# fDrive_RP2040.net
KiCad netlist of a schematic drawn in EAGLE
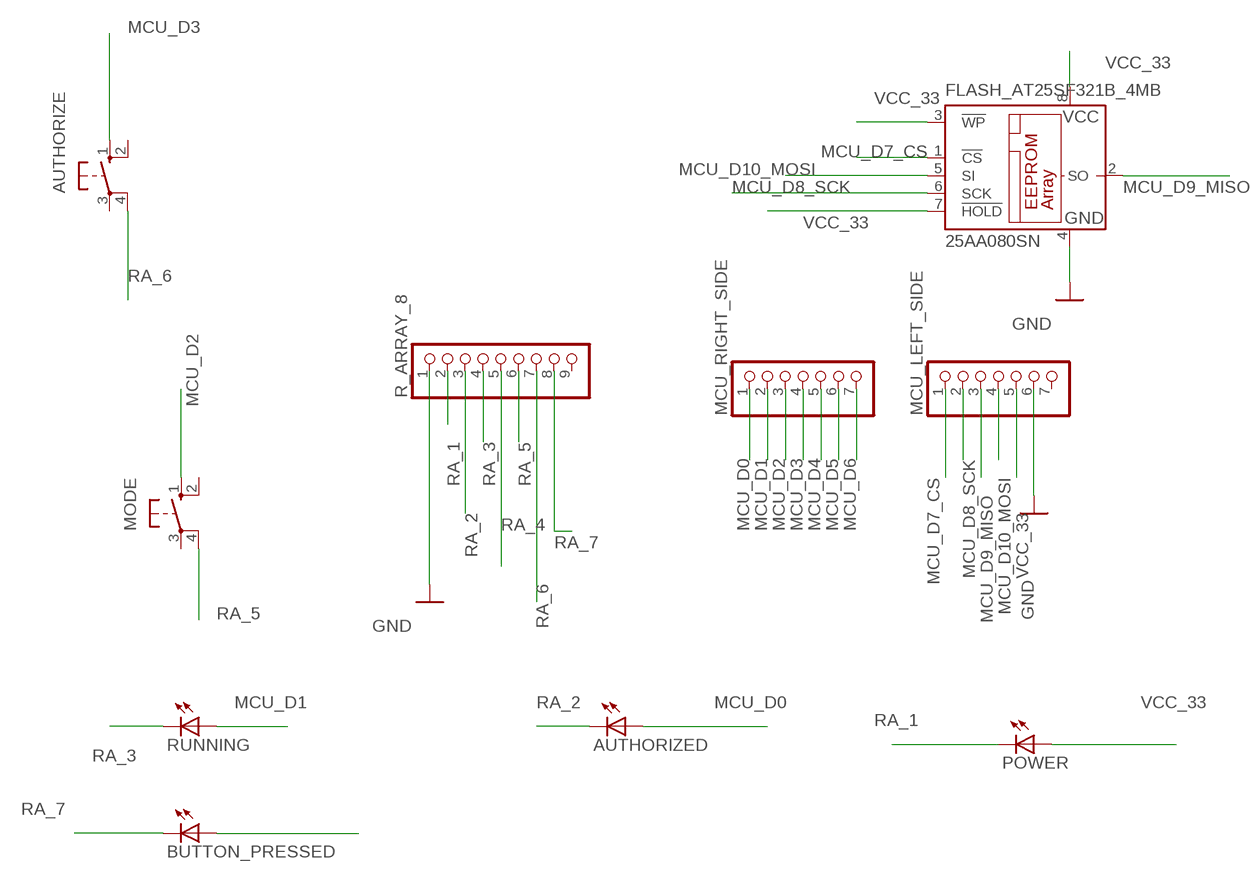
[diagram p0: schematic, sheet 1]

(export (version "E")
  (design (tool "Eeschema 10.0.6"))
  (components
    (comp (ref "AUTHORIZE")
      (value "10-XX")
      (footprint "eagle-import:B3F-10XX")
      (fields (field (name "MPN") "B3F-1000"))
      (libsource (lib "eagle-import") (part "10-XX"))
    )
    (comp (ref "AUTHORIZED")
      (value "LEDSMT1206")
      (footprint "eagle-import:1206")
      (libsource (lib "eagle-import") (part "LEDSMT1206"))
    )
    (comp (ref "BUTTON_PRESSED")
      (value "LEDSMT1206")
      (footprint "eagle-import:1206")
      (libsource (lib "eagle-import") (part "LEDSMT1206"))
    )
    (comp (ref "FLASH_AT25SF321B_4MB")
      (value "25AA080SN")
      (footprint "eagle-import:SO-08")
      (fields (field (name "MF") "MICROCHIP") (field (name "MPN") "25AA080/SN"))
      (libsource (lib "eagle-import") (part "25SNAA080"))
    )
    (comp (ref "MCU_LEFT_SIDE")
      (value "PINHD-1X7")
      (footprint "eagle-import:1X07")
      (libsource (lib "eagle-import") (part "PINHD-1X7"))
    )
    (comp (ref "MCU_RIGHT_SIDE")
      (value "PINHD-1X7")
      (footprint "eagle-import:1X07")
      (libsource (lib "eagle-import") (part "PINHD-1X7"))
    )
    (comp (ref "MODE")
      (value "10-XX")
      (footprint "eagle-import:B3F-10XX")
      (fields (field (name "MPN") "B3F-1000"))
      (libsource (lib "eagle-import") (part "10-XX"))
    )
    (comp (ref "POWER")
      (value "LEDSMT1206")
      (footprint "eagle-import:1206")
      (libsource (lib "eagle-import") (part "LEDSMT1206"))
    )
    (comp (ref "RUNNING")
      (value "LEDSMT1206")
      (footprint "eagle-import:1206")
      (libsource (lib "eagle-import") (part "LEDSMT1206"))
    )
    (comp (ref "R_ARRAY_8")
      (value "PINHD-1X9")
      (footprint "eagle-import:1X09-BIG")
      (libsource (lib "eagle-import") (part "PINHD-1X9"))
    )
  )
  (nets
    (net (code "1") (name "/MCU_D0") (class "Default")
      (node (ref "AUTHORIZED") (pin "A") (pinfunction "A_A") (pintype "passive"))
      (node (ref "MCU_RIGHT_SIDE") (pin "1") (pinfunction "1_1") (pintype "passive"))
    )
    (net (code "2") (name "/MCU_D1") (class "Default")
      (node (ref "MCU_RIGHT_SIDE") (pin "2") (pinfunction "2_2") (pintype "passive"))
      (node (ref "RUNNING") (pin "A") (pinfunction "A_A") (pintype "passive"))
    )
    (net (code "3") (name "/MCU_D2") (class "Default")
      (node (ref "MCU_RIGHT_SIDE") (pin "3") (pinfunction "3_3") (pintype "passive"))
      (node (ref "MODE") (pin "1") (pinfunction "S_1") (pintype "passive"))
    )
    (net (code "4") (name "/MCU_D3") (class "Default")
      (node (ref "AUTHORIZE") (pin "1") (pinfunction "S_1") (pintype "passive"))
      (node (ref "MCU_RIGHT_SIDE") (pin "4") (pinfunction "4_4") (pintype "passive"))
    )
    (net (code "5") (name "/MCU_D4") (class "Default")
      (node (ref "BUTTON_PRESSED") (pin "A") (pinfunction "A_A") (pintype "passive"))
      (node (ref "MCU_RIGHT_SIDE") (pin "5") (pinfunction "5_5") (pintype "passive"))
    )
    (net (code "6") (name "/MCU_D5") (class "Default")
      (node (ref "MCU_RIGHT_SIDE") (pin "6") (pinfunction "6_6") (pintype "passive"))
    )
    (net (code "7") (name "/MCU_D6") (class "Default")
      (node (ref "MCU_RIGHT_SIDE") (pin "7") (pinfunction "7_7") (pintype "passive"))
    )
    (net (code "8") (name "/MCU_D7_CS") (class "Default")
      (node (ref "FLASH_AT25SF321B_4MB") (pin "1") (pinfunction "~{CS}_1") (pintype "input"))
      (node (ref "MCU_LEFT_SIDE") (pin "1") (pinfunction "1_1") (pintype "passive"))
    )
    (net (code "9") (name "/MCU_D8_SCK") (class "Default")
      (node (ref "FLASH_AT25SF321B_4MB") (pin "6") (pinfunction "SCK_6") (pintype "input"))
      (node (ref "MCU_LEFT_SIDE") (pin "2") (pinfunction "2_2") (pintype "passive"))
    )
    (net (code "10") (name "/MCU_D9_MISO") (class "Default")
      (node (ref "FLASH_AT25SF321B_4MB") (pin "2") (pinfunction "SO_2") (pintype "bidirectional"))
      (node (ref "MCU_LEFT_SIDE") (pin "3") (pinfunction "3_3") (pintype "passive"))
    )
    (net (code "11") (name "/MCU_D10_MOSI") (class "Default")
      (node (ref "FLASH_AT25SF321B_4MB") (pin "5") (pinfunction "SI_5") (pintype "input"))
      (node (ref "MCU_LEFT_SIDE") (pin "4") (pinfunction "4_4") (pintype "passive"))
    )
    (net (code "12") (name "/RA_1") (class "Default")
      (node (ref "POWER") (pin "C") (pinfunction "C_C") (pintype "passive"))
      (node (ref "R_ARRAY_8") (pin "2") (pinfunction "2_2") (pintype "passive"))
    )
    (net (code "13") (name "/RA_2") (class "Default")
      (node (ref "AUTHORIZED") (pin "C") (pinfunction "C_C") (pintype "passive"))
      (node (ref "R_ARRAY_8") (pin "3") (pinfunction "3_3") (pintype "passive"))
    )
    (net (code "14") (name "/RA_3") (class "Default")
      (node (ref "RUNNING") (pin "C") (pinfunction "C_C") (pintype "passive"))
      (node (ref "R_ARRAY_8") (pin "4") (pinfunction "4_4") (pintype "passive"))
    )
    (net (code "15") (name "/RA_4") (class "Default")
      (node (ref "R_ARRAY_8") (pin "5") (pinfunction "5_5") (pintype "passive"))
    )
    (net (code "16") (name "/RA_5") (class "Default")
      (node (ref "MODE") (pin "4") (pinfunction "P1_4") (pintype "passive"))
      (node (ref "R_ARRAY_8") (pin "6") (pinfunction "6_6") (pintype "passive"))
    )
    (net (code "17") (name "/RA_6") (class "Default")
      (node (ref "AUTHORIZE") (pin "4") (pinfunction "P1_4") (pintype "passive"))
      (node (ref "R_ARRAY_8") (pin "7") (pinfunction "7_7") (pintype "passive"))
    )
    (net (code "18") (name "/RA_7") (class "Default")
      (node (ref "BUTTON_PRESSED") (pin "C") (pinfunction "C_C") (pintype "passive"))
      (node (ref "R_ARRAY_8") (pin "8") (pinfunction "8_8") (pintype "passive"))
    )
    (net (code "19") (name "/VCC_33") (class "Default")
      (node (ref "FLASH_AT25SF321B_4MB") (pin "3") (pinfunction "~{WP}_3") (pintype "input"))
      (node (ref "FLASH_AT25SF321B_4MB") (pin "7") (pinfunction "~{HOLD}_7") (pintype "input"))
      (node (ref "FLASH_AT25SF321B_4MB") (pin "8") (pinfunction "VCC_8") (pintype "power_in"))
      (node (ref "MCU_LEFT_SIDE") (pin "5") (pinfunction "5_5") (pintype "passive"))
      (node (ref "POWER") (pin "A") (pinfunction "A_A") (pintype "passive"))
    )
    (net (code "20") (name "GND") (class "Default")
      (node (ref "FLASH_AT25SF321B_4MB") (pin "4") (pinfunction "GND_4") (pintype "power_in"))
      (node (ref "MCU_LEFT_SIDE") (pin "6") (pinfunction "6_6") (pintype "passive"))
      (node (ref "R_ARRAY_8") (pin "1") (pinfunction "1_1") (pintype "passive"))
    )
    (net (code "21") (name "unconnected-(AUTHORIZE-P-Pad3)") (class "Default")
      (node (ref "AUTHORIZE") (pin "3") (pinfunction "P_3") (pintype "passive"))
    )
    (net (code "22") (name "unconnected-(AUTHORIZE-S1-Pad2)") (class "Default")
      (node (ref "AUTHORIZE") (pin "2") (pinfunction "S1_2") (pintype "passive"))
    )
    (net (code "23") (name "unconnected-(MCU_LEFT_SIDE-Pad7)") (class "Default")
      (node (ref "MCU_LEFT_SIDE") (pin "7") (pinfunction "7_7") (pintype "passive"))
    )
    (net (code "24") (name "unconnected-(MODE-P-Pad3)") (class "Default")
      (node (ref "MODE") (pin "3") (pinfunction "P_3") (pintype "passive"))
    )
    (net (code "25") (name "unconnected-(MODE-S1-Pad2)") (class "Default")
      (node (ref "MODE") (pin "2") (pinfunction "S1_2") (pintype "passive"))
    )
    (net (code "26") (name "unconnected-(R_ARRAY_8-Pad9)") (class "Default")
      (node (ref "R_ARRAY_8") (pin "9") (pinfunction "9_9") (pintype "passive"))
    )
  )
)
